# ESP32-S3.net
KiCad netlist of a schematic drawn in Altium Designer
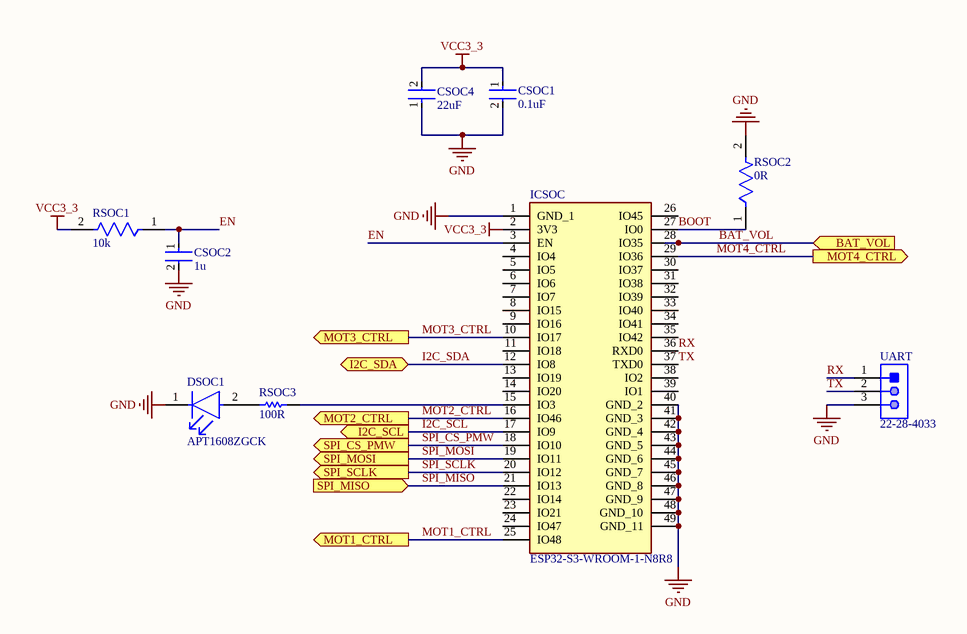
[diagram p0: ESP32-S3.SchDoc]

(export (version "E")
  (design (tool "Eeschema 10.0.6"))
  (components
    (comp (ref "CSOC1")
      (value "0.1uF")
      (footprint "FP-CL10-IPC_C")
      (description "Cap Ceramic 100nF 50V X7R ±20% Pad SMD 0603 +125°C T/R")
      (fields (field (name "TOLERANCE") "20%"))
      (libsource (lib "Altium Content Vault") (part "b4654b650e69147ec39a6b967a45e02"))
    )
    (comp (ref "CSOC2")
      (value "1u")
      (footprint "FP-CL10-IPC_A")
      (description "Cap Ceramic 1uF 25V X5R ±10% Pad SMD 0603 +85°C T/R")
      (fields (field (name "TOLERANCE") "10%"))
      (libsource (lib "Altium Content Vault") (part "b4654b650e69147ec39a6b967a45e02"))
    )
    (comp (ref "CSOC4")
      (value "22uF")
      (footprint "FP-GRM188-0_2-IPC_C")
      (description "Chip Multilayer Ceramic Capacitors for General Purpose, 0603, 22uF, X5R, 15%, 20%, 10V")
      (fields (field (name "TOLERANCE") "20%"))
      (libsource (lib "Altium Content Vault") (part "11868f565c42a9108669ba33697ecf6"))
    )
    (comp (ref "DSOC1")
      (value "APT1608ZGCK")
      (footprint "FP-APT1608ZGCK-MFG")
      (description "LED GREEN CLEAR CHIP SMD")
      (libsource (lib "Altium Content Vault") (part "8706943c75ba83719d021d2fdc84c58"))
    )
    (comp (ref "ICSOC")
      (value "ESP32-S3-WROOM-1-N8R8")
      (footprint "ESP32S3WROOM1N8R8")
      (description "Integrated Circuit")
      (libsource (lib "James Whitehead") (part "ESP32-S3-WROOM-1-N8R8"))
    )
    (comp (ref "RSOC1")
      (value "10k")
      (footprint "FP-ERJ3G-IPC_C")
      (description "RES SMD 10K OHM 5% 1/10W 0603")
      (fields (field (name "TOLERANCE") "5%"))
      (libsource (lib "Altium Content Vault") (part "1029c3af85768c4190bb7ad29bc67b5"))
    )
    (comp (ref "RSOC2")
      (value "0R")
      (footprint "FP-ERJ-3GEY0R00V-MFG")
      (description "0 Ohms Jumper 0.1W, 1/10W Chip Resistor 0603 (1608 Metric) Automotive AEC-Q200 Thick Film")
      (fields (field (name "TOLERANCE") "5%"))
      (libsource (lib "Altium Content Vault") (part "1029c3af85768c4190bb7ad29bc67b5"))
    )
    (comp (ref "RSOC3")
      (value "100R")
      (footprint "RESC1608X55X30LL15T15")
      (fields (field (name "MANUFACTURER") "Panasonic") (field (name "PART NUMBER") "ERJ-3EKF1000V"))
      (libsource (lib "Altium Content Vault") (part "RES"))
    )
    (comp (ref "UART")
      (value "22-28-4033")
      (footprint "MOLX-22-28-4033_V")
      (description "Male Header, Pitch 2.54 mm, 1 x 3 Position, Height 8.38 mm, Tail Length 3.18 mm, RoHS, Bulk")
      (fields (field (name "MANUFACTURER") "Molex"))
      (libsource (lib "Altium Content Vault") (part "CN-1P-M-R3"))
    )
  )
  (nets
    (net (code "1") (name "/BAT_VOL") (class "Default")
      (node (ref "ICSOC") (pin "28") (pinfunction "IO35_28") (pintype "passive"))
    )
    (net (code "2") (name "/BOOT") (class "Default")
      (node (ref "ICSOC") (pin "27") (pinfunction "IO0_27") (pintype "passive"))
      (node (ref "RSOC2") (pin "1") (pinfunction "1_1") (pintype "passive"))
    )
    (net (code "3") (name "/EN") (class "Default")
      (node (ref "CSOC2") (pin "1") (pinfunction "1_1") (pintype "passive"))
      (node (ref "ICSOC") (pin "3") (pinfunction "EN_3") (pintype "passive"))
      (node (ref "RSOC1") (pin "1") (pinfunction "1_1") (pintype "passive"))
    )
    (net (code "4") (name "/I2C_SCL") (class "Default")
      (node (ref "ICSOC") (pin "17") (pinfunction "IO9_17") (pintype "passive"))
    )
    (net (code "5") (name "/I2C_SDA") (class "Default")
      (node (ref "ICSOC") (pin "12") (pinfunction "IO8_12") (pintype "passive"))
    )
    (net (code "6") (name "/MOT1_CTRL") (class "Default")
      (node (ref "ICSOC") (pin "25") (pinfunction "IO48_25") (pintype "passive"))
    )
    (net (code "7") (name "/MOT2_CTRL") (class "Default")
      (node (ref "ICSOC") (pin "16") (pinfunction "IO46_16") (pintype "passive"))
    )
    (net (code "8") (name "/MOT3_CTRL") (class "Default")
      (node (ref "ICSOC") (pin "10") (pinfunction "IO17_10") (pintype "passive"))
    )
    (net (code "9") (name "/MOT4_CTRL") (class "Default")
      (node (ref "ICSOC") (pin "29") (pinfunction "IO36_29") (pintype "passive"))
    )
    (net (code "10") (name "/RX") (class "Default")
      (node (ref "ICSOC") (pin "36") (pinfunction "RXD0_36") (pintype "passive"))
      (node (ref "UART") (pin "1") (pinfunction "1_1") (pintype "passive"))
    )
    (net (code "11") (name "/SPI_CS_PMW") (class "Default")
      (node (ref "ICSOC") (pin "18") (pinfunction "IO10_18") (pintype "passive"))
    )
    (net (code "12") (name "/SPI_MISO") (class "Default")
      (node (ref "ICSOC") (pin "21") (pinfunction "IO13_21") (pintype "passive"))
    )
    (net (code "13") (name "/SPI_MOSI") (class "Default")
      (node (ref "ICSOC") (pin "19") (pinfunction "IO11_19") (pintype "passive"))
    )
    (net (code "14") (name "/SPI_SCLK") (class "Default")
      (node (ref "ICSOC") (pin "20") (pinfunction "IO12_20") (pintype "passive"))
    )
    (net (code "15") (name "/TX") (class "Default")
      (node (ref "ICSOC") (pin "37") (pinfunction "TXD0_37") (pintype "passive"))
      (node (ref "UART") (pin "2") (pinfunction "2_2") (pintype "passive"))
    )
    (net (code "16") (name "GND") (class "Default")
      (node (ref "CSOC1") (pin "2") (pinfunction "2_2") (pintype "passive"))
      (node (ref "CSOC2") (pin "2") (pinfunction "2_2") (pintype "passive"))
      (node (ref "CSOC4") (pin "1") (pinfunction "1_1") (pintype "passive"))
      (node (ref "DSOC1") (pin "1") (pinfunction "C_1") (pintype "passive"))
      (node (ref "ICSOC") (pin "1") (pinfunction "GND_1_1") (pintype "passive"))
      (node (ref "ICSOC") (pin "40") (pinfunction "GND_2_40") (pintype "passive"))
      (node (ref "ICSOC") (pin "41") (pinfunction "GND_3_41") (pintype "passive"))
      (node (ref "ICSOC") (pin "42") (pinfunction "GND_4_42") (pintype "passive"))
      (node (ref "ICSOC") (pin "43") (pinfunction "GND_5_43") (pintype "passive"))
      (node (ref "ICSOC") (pin "44") (pinfunction "GND_6_44") (pintype "passive"))
      (node (ref "ICSOC") (pin "45") (pinfunction "GND_7_45") (pintype "passive"))
      (node (ref "ICSOC") (pin "46") (pinfunction "GND_8_46") (pintype "passive"))
      (node (ref "ICSOC") (pin "47") (pinfunction "GND_9_47") (pintype "passive"))
      (node (ref "ICSOC") (pin "48") (pinfunction "GND_10_48") (pintype "passive"))
      (node (ref "ICSOC") (pin "49") (pinfunction "GND_11_49") (pintype "passive"))
      (node (ref "RSOC2") (pin "2") (pinfunction "2_2") (pintype "passive"))
      (node (ref "UART") (pin "3") (pinfunction "3_3") (pintype "passive"))
    )
    (net (code "17") (name "Net-(DSOC1-A)") (class "Default")
      (node (ref "DSOC1") (pin "2") (pinfunction "A_2") (pintype "passive"))
      (node (ref "RSOC3") (pin "2") (pinfunction "2_2") (pintype "passive"))
    )
    (net (code "18") (name "Net-(ICSOC-IO3)") (class "Default")
      (node (ref "ICSOC") (pin "15") (pinfunction "IO3_15") (pintype "passive"))
      (node (ref "RSOC3") (pin "1") (pinfunction "1_1") (pintype "passive"))
    )
    (net (code "19") (name "VCC3_3") (class "Default")
      (node (ref "CSOC1") (pin "1") (pinfunction "1_1") (pintype "passive"))
      (node (ref "CSOC4") (pin "2") (pinfunction "2_2") (pintype "passive"))
      (node (ref "ICSOC") (pin "2") (pinfunction "3V3_2") (pintype "passive"))
      (node (ref "RSOC1") (pin "2") (pinfunction "2_2") (pintype "passive"))
    )
    (net (code "20") (name "unconnected-(ICSOC-IO1-Pad39)") (class "Default")
      (node (ref "ICSOC") (pin "39") (pinfunction "IO1_39") (pintype "passive"))
    )
    (net (code "21") (name "unconnected-(ICSOC-IO2-Pad38)") (class "Default")
      (node (ref "ICSOC") (pin "38") (pinfunction "IO2_38") (pintype "passive"))
    )
    (net (code "22") (name "unconnected-(ICSOC-IO4-Pad4)") (class "Default")
      (node (ref "ICSOC") (pin "4") (pinfunction "IO4_4") (pintype "passive"))
    )
    (net (code "23") (name "unconnected-(ICSOC-IO5-Pad5)") (class "Default")
      (node (ref "ICSOC") (pin "5") (pinfunction "IO5_5") (pintype "passive"))
    )
    (net (code "24") (name "unconnected-(ICSOC-IO6-Pad6)") (class "Default")
      (node (ref "ICSOC") (pin "6") (pinfunction "IO6_6") (pintype "passive"))
    )
    (net (code "25") (name "unconnected-(ICSOC-IO7-Pad7)") (class "Default")
      (node (ref "ICSOC") (pin "7") (pinfunction "IO7_7") (pintype "passive"))
    )
    (net (code "26") (name "unconnected-(ICSOC-IO14-Pad22)") (class "Default")
      (node (ref "ICSOC") (pin "22") (pinfunction "IO14_22") (pintype "passive"))
    )
    (net (code "27") (name "unconnected-(ICSOC-IO15-Pad8)") (class "Default")
      (node (ref "ICSOC") (pin "8") (pinfunction "IO15_8") (pintype "passive"))
    )
    (net (code "28") (name "unconnected-(ICSOC-IO16-Pad9)") (class "Default")
      (node (ref "ICSOC") (pin "9") (pinfunction "IO16_9") (pintype "passive"))
    )
    (net (code "29") (name "unconnected-(ICSOC-IO18-Pad11)") (class "Default")
      (node (ref "ICSOC") (pin "11") (pinfunction "IO18_11") (pintype "passive"))
    )
    (net (code "30") (name "unconnected-(ICSOC-IO19-Pad13)") (class "Default")
      (node (ref "ICSOC") (pin "13") (pinfunction "IO19_13") (pintype "passive"))
    )
    (net (code "31") (name "unconnected-(ICSOC-IO20-Pad14)") (class "Default")
      (node (ref "ICSOC") (pin "14") (pinfunction "IO20_14") (pintype "passive"))
    )
    (net (code "32") (name "unconnected-(ICSOC-IO21-Pad23)") (class "Default")
      (node (ref "ICSOC") (pin "23") (pinfunction "IO21_23") (pintype "passive"))
    )
    (net (code "33") (name "unconnected-(ICSOC-IO37-Pad30)") (class "Default")
      (node (ref "ICSOC") (pin "30") (pinfunction "IO37_30") (pintype "passive"))
    )
    (net (code "34") (name "unconnected-(ICSOC-IO38-Pad31)") (class "Default")
      (node (ref "ICSOC") (pin "31") (pinfunction "IO38_31") (pintype "passive"))
    )
    (net (code "35") (name "unconnected-(ICSOC-IO39-Pad32)") (class "Default")
      (node (ref "ICSOC") (pin "32") (pinfunction "IO39_32") (pintype "passive"))
    )
    (net (code "36") (name "unconnected-(ICSOC-IO40-Pad33)") (class "Default")
      (node (ref "ICSOC") (pin "33") (pinfunction "IO40_33") (pintype "passive"))
    )
    (net (code "37") (name "unconnected-(ICSOC-IO41-Pad34)") (class "Default")
      (node (ref "ICSOC") (pin "34") (pinfunction "IO41_34") (pintype "passive"))
    )
    (net (code "38") (name "unconnected-(ICSOC-IO42-Pad35)") (class "Default")
      (node (ref "ICSOC") (pin "35") (pinfunction "IO42_35") (pintype "passive"))
    )
    (net (code "39") (name "unconnected-(ICSOC-IO45-Pad26)") (class "Default")
      (node (ref "ICSOC") (pin "26") (pinfunction "IO45_26") (pintype "passive"))
    )
    (net (code "40") (name "unconnected-(ICSOC-IO47-Pad24)") (class "Default")
      (node (ref "ICSOC") (pin "24") (pinfunction "IO47_24") (pintype "passive"))
    )
  )
)
